# VJ111.net
KiCad netlist of a schematic drawn in Altium Designer
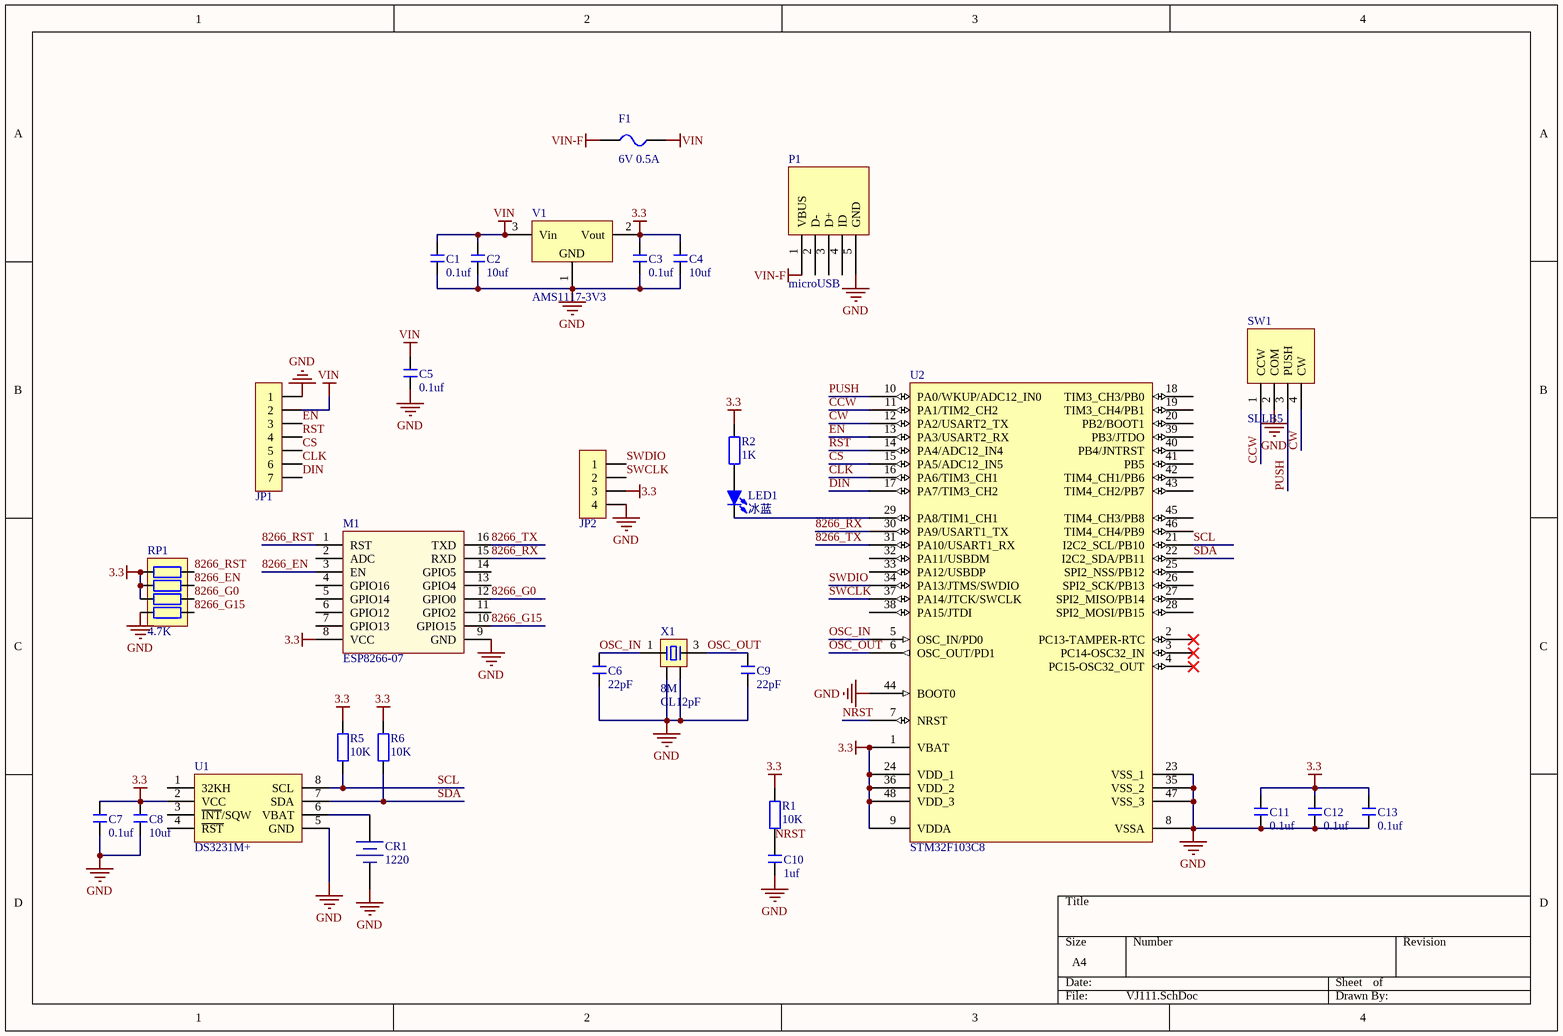
[diagram p0: VJ111.SchDoc]

(export (version "E")
  (design (tool "Eeschema 10.0.6"))
  (components
    (comp (ref "C1")
      (value "0.1uf")
      (footprint "C 0603_L")
      (description "无极性贴片电容")
      (fields (field (name "版权归属") "源创客"))
      (libsource (lib "3.1   - 电阻-电容-电感") (part "C"))
    )
    (comp (ref "C2")
      (value "10uf")
      (footprint "C 0603_L")
      (description "无极性贴片电容")
      (fields (field (name "版权归属") "源创客"))
      (libsource (lib "3.1   - 电阻-电容-电感") (part "C"))
    )
    (comp (ref "C3")
      (value "0.1uf")
      (footprint "C 0603_L")
      (description "无极性贴片电容")
      (fields (field (name "版权归属") "源创客"))
      (libsource (lib "3.1   - 电阻-电容-电感") (part "C"))
    )
    (comp (ref "C4")
      (value "10uf")
      (footprint "C 0603_L")
      (description "无极性贴片电容")
      (fields (field (name "版权归属") "源创客"))
      (libsource (lib "3.1   - 电阻-电容-电感") (part "C"))
    )
    (comp (ref "C5")
      (value "0.1uf")
      (footprint "C 0603_L")
      (description "无极性贴片电容")
      (fields (field (name "版权归属") "源创客"))
      (libsource (lib "3.1   - 电阻-电容-电感") (part "C"))
    )
    (comp (ref "C6")
      (value "22pF")
      (footprint "C 0603_L")
      (description "无极性贴片电容")
      (fields (field (name "版权归属") "源创客"))
      (libsource (lib "3.1   - 电阻-电容-电感") (part "C"))
    )
    (comp (ref "C7")
      (value "0.1uf")
      (footprint "C 0603_L")
      (description "无极性贴片电容")
      (fields (field (name "版权归属") "源创客"))
      (libsource (lib "3.1   - 电阻-电容-电感") (part "C"))
    )
    (comp (ref "C8")
      (value "10uf")
      (footprint "C 0603_L")
      (description "无极性贴片电容")
      (fields (field (name "版权归属") "源创客"))
      (libsource (lib "3.1   - 电阻-电容-电感") (part "C"))
    )
    (comp (ref "C9")
      (value "22pF")
      (footprint "C 0603_L")
      (description "无极性贴片电容")
      (fields (field (name "版权归属") "源创客"))
      (libsource (lib "3.1   - 电阻-电容-电感") (part "C"))
    )
    (comp (ref "C10")
      (value "1uf")
      (footprint "C 0603_L")
      (description "无极性贴片电容")
      (fields (field (name "版权归属") "源创客"))
      (libsource (lib "3.1   - 电阻-电容-电感") (part "C"))
    )
    (comp (ref "C11")
      (value "0.1uf")
      (footprint "C 0603_L")
      (description "无极性贴片电容")
      (fields (field (name "版权归属") "源创客"))
      (libsource (lib "3.1   - 电阻-电容-电感") (part "C"))
    )
    (comp (ref "C12")
      (value "0.1uf")
      (footprint "C 0603_L")
      (description "无极性贴片电容")
      (fields (field (name "版权归属") "源创客"))
      (libsource (lib "3.1   - 电阻-电容-电感") (part "C"))
    )
    (comp (ref "C13")
      (value "0.1uf")
      (footprint "C 0603_L")
      (description "无极性贴片电容")
      (fields (field (name "版权归属") "源创客"))
      (libsource (lib "3.1   - 电阻-电容-电感") (part "C"))
    )
    (comp (ref "CR1")
      (value "1220")
      (footprint "CR1220_A")
      (description "微型电池")
      (fields (field (name "版权归属") "源创客"))
      (libsource (lib "15.1 - 未分类器件") (part "CR-3V"))
    )
    (comp (ref "F1")
      (value "6V 0.5A")
      (footprint "FU 0805")
      (description "贴片保险丝")
      (fields (field (name "版权归属") "源创客"))
      (libsource (lib "10.1 - 保险丝-晶振") (part "FU"))
    )
    (comp (ref "JP1")
      (value "HDR-1X7")
      (footprint "HDR2.54-LI-7P")
      (description "7P接插件")
      (fields (field (name "版权归属") "源创客"))
      (libsource (lib "4.6   - 接插件-脚距2.54") (part "Header 7"))
    )
    (comp (ref "JP2")
      (value "HDR-1X4")
      (footprint "HDR2.54-LI-4P")
      (description "4P接插件")
      (fields (field (name "版权归属") "源创客"))
      (libsource (lib "4.6   - 接插件-脚距2.54") (part "Header 4"))
    )
    (comp (ref "LED1")
      (value "冰蓝")
      (footprint "LED 0603B")
      (description "贴片LED")
      (fields (field (name "版权归属") "源创客"))
      (libsource (lib "9.1   - LED") (part "LED-SMD"))
    )
    (comp (ref "M1")
      (value "ESP8266-07")
      (footprint "ESP-07")
      (description "串口 WIFI模块，ESP-07")
      (fields (field (name "版权归属") "源创客"))
      (libsource (lib "13.1 - 模块") (part "ESP8266-07"))
    )
    (comp (ref "P1") (value "microUSB") (footprint "microUSB") (libsource (lib "自建库") (part "microUSB")))
    (comp (ref "R1")
      (value "10K")
      (footprint "R 0603_L")
      (description "贴片电阻")
      (fields (field (name "版权归属") "源创客"))
      (libsource (lib "3.1   - 电阻-电容-电感") (part "R"))
    )
    (comp (ref "R2")
      (value "1K")
      (footprint "R 0603_L")
      (description "贴片电阻")
      (fields (field (name "版权归属") "源创客"))
      (libsource (lib "3.1   - 电阻-电容-电感") (part "R"))
    )
    (comp (ref "R5")
      (value "10K")
      (footprint "R 0603_L")
      (description "贴片电阻")
      (fields (field (name "版权归属") "源创客"))
      (libsource (lib "3.1   - 电阻-电容-电感") (part "R"))
    )
    (comp (ref "R6")
      (value "10K")
      (footprint "R 0603_L")
      (description "贴片电阻")
      (fields (field (name "版权归属") "源创客"))
      (libsource (lib "3.1   - 电阻-电容-电感") (part "R"))
    )
    (comp (ref "RP1")
      (value "4.7K")
      (footprint "RCA-8P4R-0603")
      (description "贴片网络排阻")
      (fields (field (name "版权归属") "源创客"))
      (libsource (lib "3.1   - 电阻-电容-电感") (part "R-8P4R"))
    )
    (comp (ref "SW1")
      (value "SLLB5")
      (footprint "SLLB510100")
      (description "操作杆和按动操作型开关")
      (libsource (lib "自建库") (part "SLLB5"))
    )
    (comp (ref "U1") (value "DS3231M+") (footprint "SOP8_N") (libsource (lib "自建库") (part "DS3231M+")))
    (comp (ref "U2")
      (value "STM32F103C8")
      (footprint "LQFP48 7X7_N")
      (description "Flaah:64/RAM:20/IO:36")
      (fields (field (name "版权归属") "源创客"))
      (libsource (lib "2.1   - STM32系列单片机") (part "STM32F103C8"))
    )
    (comp (ref "V1")
      (value "AMS1117-3V3")
      (footprint "SOT223_L")
      (description "三端稳压芯片")
      (fields (field (name "版权归属") "源创客"))
      (libsource (lib "1.3   - 电源类芯片") (part "AMS1117"))
    )
    (comp (ref "X1")
      (value "8M")
      (footprint "OSC 3225-4P")
      (description "4脚无源晶振")
      (fields (field (name "负载电容") "CL12pF") (field (name "版权归属") "源创客"))
      (libsource (lib "10.1 - 保险丝-晶振") (part "XTAL-4P"))
    )
  )
  (nets
    (net (code "1") (name "/8266_EN") (class "Default")
      (node (ref "M1") (pin "3") (pinfunction "EN_3") (pintype "passive"))
      (node (ref "RP1") (pin "7") (pinfunction "7_7") (pintype "passive"))
    )
    (net (code "2") (name "/8266_G0") (class "Default")
      (node (ref "M1") (pin "12") (pinfunction "GPIO0_12") (pintype "passive"))
      (node (ref "RP1") (pin "6") (pinfunction "6_6") (pintype "passive"))
    )
    (net (code "3") (name "/8266_G15") (class "Default")
      (node (ref "M1") (pin "10") (pinfunction "GPIO15_10") (pintype "passive"))
      (node (ref "RP1") (pin "5") (pinfunction "5_5") (pintype "passive"))
    )
    (net (code "4") (name "/8266_RST") (class "Default")
      (node (ref "M1") (pin "1") (pinfunction "RST_1") (pintype "passive"))
      (node (ref "RP1") (pin "8") (pinfunction "8_8") (pintype "passive"))
    )
    (net (code "5") (name "/8266_RX") (class "Default")
      (node (ref "M1") (pin "15") (pinfunction "RXD_15") (pintype "passive"))
      (node (ref "U2") (pin "30") (pinfunction "PA9/USART1_TX_30") (pintype "bidirectional"))
    )
    (net (code "6") (name "/8266_TX") (class "Default")
      (node (ref "M1") (pin "16") (pinfunction "TXD_16") (pintype "passive"))
      (node (ref "U2") (pin "31") (pinfunction "PA10/USART1_RX_31") (pintype "bidirectional"))
    )
    (net (code "7") (name "/CCW") (class "Default")
      (node (ref "SW1") (pin "1") (pinfunction "CCW_1") (pintype "passive"))
      (node (ref "U2") (pin "11") (pinfunction "PA1/TIM2_CH2_11") (pintype "bidirectional"))
    )
    (net (code "8") (name "/CLK") (class "Default")
      (node (ref "JP1") (pin "6") (pinfunction "6_6") (pintype "passive"))
      (node (ref "U2") (pin "16") (pinfunction "PA6/TIM3_CH1_16") (pintype "bidirectional"))
    )
    (net (code "9") (name "/CS") (class "Default")
      (node (ref "JP1") (pin "5") (pinfunction "5_5") (pintype "passive"))
      (node (ref "U2") (pin "15") (pinfunction "PA5/ADC12_IN5_15") (pintype "bidirectional"))
    )
    (net (code "10") (name "/CW") (class "Default")
      (node (ref "SW1") (pin "4") (pinfunction "CW_4") (pintype "passive"))
      (node (ref "U2") (pin "12") (pinfunction "PA2/USART2_TX_12") (pintype "bidirectional"))
    )
    (net (code "11") (name "/DIN") (class "Default")
      (node (ref "JP1") (pin "7") (pinfunction "7_7") (pintype "passive"))
      (node (ref "U2") (pin "17") (pinfunction "PA7/TIM3_CH2_17") (pintype "bidirectional"))
    )
    (net (code "12") (name "/EN") (class "Default")
      (node (ref "JP1") (pin "3") (pinfunction "3_3") (pintype "passive"))
      (node (ref "U2") (pin "13") (pinfunction "PA3/USART2_RX_13") (pintype "bidirectional"))
    )
    (net (code "13") (name "/NRST") (class "Default")
      (node (ref "C10") (pin "2") (pinfunction "2_2") (pintype "passive"))
      (node (ref "R1") (pin "1") (pinfunction "1_1") (pintype "passive"))
      (node (ref "U2") (pin "7") (pinfunction "NRST_7") (pintype "bidirectional"))
    )
    (net (code "14") (name "/OSC_IN") (class "Default")
      (node (ref "C6") (pin "2") (pinfunction "2_2") (pintype "passive"))
      (node (ref "U2") (pin "5") (pinfunction "OSC_IN/PD0_5") (pintype "input"))
      (node (ref "X1") (pin "1") (pinfunction "1_1") (pintype "passive"))
    )
    (net (code "15") (name "/OSC_OUT") (class "Default")
      (node (ref "C9") (pin "2") (pinfunction "2_2") (pintype "passive"))
      (node (ref "U2") (pin "6") (pinfunction "OSC_OUT/PD1_6") (pintype "output"))
      (node (ref "X1") (pin "3") (pinfunction "3_3") (pintype "passive"))
    )
    (net (code "16") (name "/PUSH") (class "Default")
      (node (ref "SW1") (pin "3") (pinfunction "PUSH_3") (pintype "passive"))
      (node (ref "U2") (pin "10") (pinfunction "PA0/WKUP/ADC12_IN0_10") (pintype "bidirectional"))
    )
    (net (code "17") (name "/RST") (class "Default")
      (node (ref "JP1") (pin "4") (pinfunction "4_4") (pintype "passive"))
      (node (ref "U2") (pin "14") (pinfunction "PA4/ADC12_IN4_14") (pintype "bidirectional"))
    )
    (net (code "18") (name "/SCL") (class "Default")
      (node (ref "R5") (pin "1") (pinfunction "1_1") (pintype "passive"))
      (node (ref "U1") (pin "8") (pinfunction "SCL_8") (pintype "passive"))
      (node (ref "U2") (pin "21") (pinfunction "I2C2_SCL/PB10_21") (pintype "bidirectional"))
    )
    (net (code "19") (name "/SDA") (class "Default")
      (node (ref "R6") (pin "1") (pinfunction "1_1") (pintype "passive"))
      (node (ref "U1") (pin "7") (pinfunction "SDA_7") (pintype "passive"))
      (node (ref "U2") (pin "22") (pinfunction "I2C2_SDA/PB11_22") (pintype "bidirectional"))
    )
    (net (code "20") (name "/SWCLK") (class "Default")
      (node (ref "JP2") (pin "2") (pinfunction "2_2") (pintype "passive"))
      (node (ref "U2") (pin "37") (pinfunction "PA14/JTCK/SWCLK_37") (pintype "bidirectional"))
    )
    (net (code "21") (name "/SWDIO") (class "Default")
      (node (ref "JP2") (pin "1") (pinfunction "1_1") (pintype "passive"))
      (node (ref "U2") (pin "34") (pinfunction "PA13/JTMS/SWDIO_34") (pintype "bidirectional"))
    )
    (net (code "22") (name "3.3") (class "Default")
      (node (ref "C11") (pin "2") (pinfunction "2_2") (pintype "passive"))
      (node (ref "C12") (pin "2") (pinfunction "2_2") (pintype "passive"))
      (node (ref "C13") (pin "2") (pinfunction "2_2") (pintype "passive"))
      (node (ref "C3") (pin "2") (pinfunction "2_2") (pintype "passive"))
      (node (ref "C4") (pin "2") (pinfunction "2_2") (pintype "passive"))
      (node (ref "C7") (pin "2") (pinfunction "2_2") (pintype "passive"))
      (node (ref "C8") (pin "2") (pinfunction "2_2") (pintype "passive"))
      (node (ref "JP2") (pin "3") (pinfunction "3_3") (pintype "passive"))
      (node (ref "M1") (pin "8") (pinfunction "VCC_8") (pintype "passive"))
      (node (ref "R1") (pin "2") (pinfunction "2_2") (pintype "passive"))
      (node (ref "R2") (pin "2") (pinfunction "2_2") (pintype "passive"))
      (node (ref "R5") (pin "2") (pinfunction "2_2") (pintype "passive"))
      (node (ref "R6") (pin "2") (pinfunction "2_2") (pintype "passive"))
      (node (ref "RP1") (pin "1") (pinfunction "1_1") (pintype "passive"))
      (node (ref "RP1") (pin "2") (pinfunction "2_2") (pintype "passive"))
      (node (ref "RP1") (pin "3") (pinfunction "3_3") (pintype "passive"))
      (node (ref "U1") (pin "2") (pinfunction "VCC_2") (pintype "passive"))
      (node (ref "U2") (pin "1") (pinfunction "VBAT_1") (pintype "power_in"))
      (node (ref "U2") (pin "24") (pinfunction "VDD_1_24") (pintype "power_in"))
      (node (ref "U2") (pin "36") (pinfunction "VDD_2_36") (pintype "power_in"))
      (node (ref "U2") (pin "48") (pinfunction "VDD_3_48") (pintype "power_in"))
      (node (ref "U2") (pin "9") (pinfunction "VDDA_9") (pintype "power_in"))
      (node (ref "V1") (pin "2") (pinfunction "Vout_2") (pintype "passive"))
    )
    (net (code "23") (name "GND") (class "Default")
      (node (ref "C1") (pin "1") (pinfunction "1_1") (pintype "passive"))
      (node (ref "C10") (pin "1") (pinfunction "1_1") (pintype "passive"))
      (node (ref "C11") (pin "1") (pinfunction "1_1") (pintype "passive"))
      (node (ref "C12") (pin "1") (pinfunction "1_1") (pintype "passive"))
      (node (ref "C13") (pin "1") (pinfunction "1_1") (pintype "passive"))
      (node (ref "C2") (pin "1") (pinfunction "1_1") (pintype "passive"))
      (node (ref "C3") (pin "1") (pinfunction "1_1") (pintype "passive"))
      (node (ref "C4") (pin "1") (pinfunction "1_1") (pintype "passive"))
      (node (ref "C5") (pin "2") (pinfunction "2_2") (pintype "passive"))
      (node (ref "C6") (pin "1") (pinfunction "1_1") (pintype "passive"))
      (node (ref "C7") (pin "1") (pinfunction "1_1") (pintype "passive"))
      (node (ref "C8") (pin "1") (pinfunction "1_1") (pintype "passive"))
      (node (ref "C9") (pin "1") (pinfunction "1_1") (pintype "passive"))
      (node (ref "CR1") (pin "2") (pinfunction "DC-_2") (pintype "passive"))
      (node (ref "JP1") (pin "1") (pinfunction "1_1") (pintype "passive"))
      (node (ref "JP2") (pin "4") (pinfunction "4_4") (pintype "passive"))
      (node (ref "M1") (pin "9") (pinfunction "GND_9") (pintype "passive"))
      (node (ref "P1") (pin "5") (pinfunction "GND_5") (pintype "passive"))
      (node (ref "RP1") (pin "4") (pinfunction "4_4") (pintype "passive"))
      (node (ref "SW1") (pin "2") (pinfunction "COM_2") (pintype "passive"))
      (node (ref "U1") (pin "5") (pinfunction "GND_5") (pintype "passive"))
      (node (ref "U2") (pin "23") (pinfunction "VSS_1_23") (pintype "power_in"))
      (node (ref "U2") (pin "35") (pinfunction "VSS_2_35") (pintype "power_in"))
      (node (ref "U2") (pin "44") (pinfunction "BOOT0_44") (pintype "input"))
      (node (ref "U2") (pin "47") (pinfunction "VSS_3_47") (pintype "power_in"))
      (node (ref "U2") (pin "8") (pinfunction "VSSA_8") (pintype "power_in"))
      (node (ref "V1") (pin "1") (pinfunction "GND_1") (pintype "passive"))
      (node (ref "X1") (pin "2") (pinfunction "2_2") (pintype "passive"))
      (node (ref "X1") (pin "4") (pinfunction "4_4") (pintype "passive"))
    )
    (net (code "24") (name "Net-(CR1-DC+)") (class "Default")
      (node (ref "CR1") (pin "1") (pinfunction "DC+_1") (pintype "passive"))
      (node (ref "U1") (pin "6") (pinfunction "VBAT_6") (pintype "passive"))
    )
    (net (code "25") (name "Net-(LED1-A)") (class "Default")
      (node (ref "LED1") (pin "1") (pinfunction "A_1") (pintype "passive"))
      (node (ref "R2") (pin "1") (pinfunction "1_1") (pintype "passive"))
    )
    (net (code "26") (name "Net-(LED1-K)") (class "Default")
      (node (ref "LED1") (pin "2") (pinfunction "K_2") (pintype "passive"))
      (node (ref "U2") (pin "29") (pinfunction "PA8/TIM1_CH1_29") (pintype "bidirectional"))
    )
    (net (code "27") (name "VIN") (class "Default")
      (node (ref "C1") (pin "2") (pinfunction "2_2") (pintype "passive"))
      (node (ref "C2") (pin "2") (pinfunction "2_2") (pintype "passive"))
      (node (ref "C5") (pin "1") (pinfunction "1_1") (pintype "passive"))
      (node (ref "F1") (pin "2") (pinfunction "2_2") (pintype "passive"))
      (node (ref "JP1") (pin "2") (pinfunction "2_2") (pintype "passive"))
      (node (ref "V1") (pin "3") (pinfunction "Vin_3") (pintype "passive"))
    )
    (net (code "28") (name "VIN-F") (class "Default")
      (node (ref "F1") (pin "1") (pinfunction "1_1") (pintype "passive"))
      (node (ref "P1") (pin "1") (pinfunction "VBUS_1") (pintype "passive"))
    )
    (net (code "29") (name "unconnected-(M1-ADC-Pad2)") (class "Default")
      (node (ref "M1") (pin "2") (pinfunction "ADC_2") (pintype "passive"))
    )
    (net (code "30") (name "unconnected-(M1-GPIO2-Pad11)") (class "Default")
      (node (ref "M1") (pin "11") (pinfunction "GPIO2_11") (pintype "passive"))
    )
    (net (code "31") (name "unconnected-(M1-GPIO4-Pad13)") (class "Default")
      (node (ref "M1") (pin "13") (pinfunction "GPIO4_13") (pintype "passive"))
    )
    (net (code "32") (name "unconnected-(M1-GPIO5-Pad14)") (class "Default")
      (node (ref "M1") (pin "14") (pinfunction "GPIO5_14") (pintype "passive"))
    )
    (net (code "33") (name "unconnected-(M1-GPIO12-Pad6)") (class "Default")
      (node (ref "M1") (pin "6") (pinfunction "GPIO12_6") (pintype "passive"))
    )
    (net (code "34") (name "unconnected-(M1-GPIO13-Pad7)") (class "Default")
      (node (ref "M1") (pin "7") (pinfunction "GPIO13_7") (pintype "passive"))
    )
    (net (code "35") (name "unconnected-(M1-GPIO14-Pad5)") (class "Default")
      (node (ref "M1") (pin "5") (pinfunction "GPIO14_5") (pintype "passive"))
    )
    (net (code "36") (name "unconnected-(M1-GPIO16-Pad4)") (class "Default")
      (node (ref "M1") (pin "4") (pinfunction "GPIO16_4") (pintype "passive"))
    )
    (net (code "37") (name "unconnected-(P1-D+-Pad3)") (class "Default")
      (node (ref "P1") (pin "3") (pinfunction "D+_3") (pintype "passive"))
    )
    (net (code "38") (name "unconnected-(P1-D--Pad2)") (class "Default")
      (node (ref "P1") (pin "2") (pinfunction "D-_2") (pintype "passive"))
    )
    (net (code "39") (name "unconnected-(P1-ID-Pad4)") (class "Default")
      (node (ref "P1") (pin "4") (pinfunction "ID_4") (pintype "passive"))
    )
    (net (code "40") (name "unconnected-(U1-32KH-Pad1)") (class "Default")
      (node (ref "U1") (pin "1") (pinfunction "32KH_1") (pintype "passive"))
    )
    (net (code "41") (name "unconnected-(U1-~{INT}{slash}SQW-Pad3)") (class "Default")
      (node (ref "U1") (pin "3") (pinfunction "~{INT}/SQW_3") (pintype "passive"))
    )
    (net (code "42") (name "unconnected-(U1-~{RST}-Pad4)") (class "Default")
      (node (ref "U1") (pin "4") (pinfunction "~{RST}_4") (pintype "passive"))
    )
    (net (code "43") (name "unconnected-(U2-PA11{slash}USBDM-Pad32)") (class "Default")
      (node (ref "U2") (pin "32") (pinfunction "PA11/USBDM_32") (pintype "bidirectional"))
    )
    (net (code "44") (name "unconnected-(U2-PA12{slash}USBDP-Pad33)") (class "Default")
      (node (ref "U2") (pin "33") (pinfunction "PA12/USBDP_33") (pintype "bidirectional"))
    )
    (net (code "45") (name "unconnected-(U2-PA15{slash}JTDI-Pad38)") (class "Default")
      (node (ref "U2") (pin "38") (pinfunction "PA15/JTDI_38") (pintype "bidirectional"))
    )
    (net (code "46") (name "unconnected-(U2-PB2{slash}BOOT1-Pad20)") (class "Default")
      (node (ref "U2") (pin "20") (pinfunction "PB2/BOOT1_20") (pintype "bidirectional"))
    )
    (net (code "47") (name "unconnected-(U2-PB3{slash}JTDO-Pad39)") (class "Default")
      (node (ref "U2") (pin "39") (pinfunction "PB3/JTDO_39") (pintype "bidirectional"))
    )
    (net (code "48") (name "unconnected-(U2-PB4{slash}JNTRST-Pad40)") (class "Default")
      (node (ref "U2") (pin "40") (pinfunction "PB4/JNTRST_40") (pintype "bidirectional"))
    )
    (net (code "49") (name "unconnected-(U2-PB5-Pad41)") (class "Default")
      (node (ref "U2") (pin "41") (pinfunction "PB5_41") (pintype "bidirectional"))
    )
    (net (code "50") (name "unconnected-(U2-PC13-TAMPER-RTC-Pad2)") (class "Default")
      (node (ref "U2") (pin "2") (pinfunction "PC13-TAMPER-RTC_2") (pintype "bidirectional+no_connect"))
    )
    (net (code "51") (name "unconnected-(U2-PC14-OSC32_IN-Pad3)") (class "Default")
      (node (ref "U2") (pin "3") (pinfunction "PC14-OSC32_IN_3") (pintype "bidirectional+no_connect"))
    )
    (net (code "52") (name "unconnected-(U2-PC15-OSC32_OUT-Pad4)") (class "Default")
      (node (ref "U2") (pin "4") (pinfunction "PC15-OSC32_OUT_4") (pintype "bidirectional+no_connect"))
    )
    (net (code "53") (name "unconnected-(U2-SPI2_MISO{slash}PB14-Pad27)") (class "Default")
      (node (ref "U2") (pin "27") (pinfunction "SPI2_MISO/PB14_27") (pintype "bidirectional"))
    )
    (net (code "54") (name "unconnected-(U2-SPI2_MOSI{slash}PB15-Pad28)") (class "Default")
      (node (ref "U2") (pin "28") (pinfunction "SPI2_MOSI/PB15_28") (pintype "bidirectional"))
    )
    (net (code "55") (name "unconnected-(U2-SPI2_NSS{slash}PB12-Pad25)") (class "Default")
      (node (ref "U2") (pin "25") (pinfunction "SPI2_NSS/PB12_25") (pintype "bidirectional"))
    )
    (net (code "56") (name "unconnected-(U2-SPI2_SCK{slash}PB13-Pad26)") (class "Default")
      (node (ref "U2") (pin "26") (pinfunction "SPI2_SCK/PB13_26") (pintype "bidirectional"))
    )
    (net (code "57") (name "unconnected-(U2-TIM3_CH3{slash}PB0-Pad18)") (class "Default")
      (node (ref "U2") (pin "18") (pinfunction "TIM3_CH3/PB0_18") (pintype "bidirectional"))
    )
    (net (code "58") (name "unconnected-(U2-TIM3_CH4{slash}PB1-Pad19)") (class "Default")
      (node (ref "U2") (pin "19") (pinfunction "TIM3_CH4/PB1_19") (pintype "bidirectional"))
    )
    (net (code "59") (name "unconnected-(U2-TIM4_CH1{slash}PB6-Pad42)") (class "Default")
      (node (ref "U2") (pin "42") (pinfunction "TIM4_CH1/PB6_42") (pintype "bidirectional"))
    )
    (net (code "60") (name "unconnected-(U2-TIM4_CH2{slash}PB7-Pad43)") (class "Default")
      (node (ref "U2") (pin "43") (pinfunction "TIM4_CH2/PB7_43") (pintype "bidirectional"))
    )
    (net (code "61") (name "unconnected-(U2-TIM4_CH3{slash}PB8-Pad45)") (class "Default")
      (node (ref "U2") (pin "45") (pinfunction "TIM4_CH3/PB8_45") (pintype "bidirectional"))
    )
    (net (code "62") (name "unconnected-(U2-TIM4_CH4{slash}PB9-Pad46)") (class "Default")
      (node (ref "U2") (pin "46") (pinfunction "TIM4_CH4/PB9_46") (pintype "bidirectional"))
    )
  )
)
